# adapter.net
KiCad netlist of a schematic drawn in EAGLE
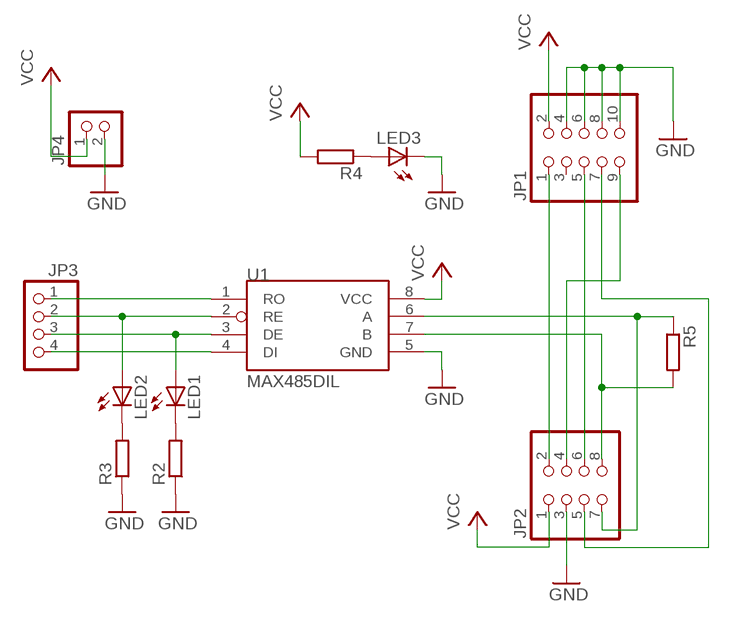
[diagram p0: schematic, sheet 1]

(export (version "E")
  (design (tool "Eeschema 10.0.6"))
  (components
    (comp (ref "JP1")
      (value "PINHD-2X5")
      (footprint "eagle-import:2X05")
      (libsource (lib "eagle-import") (part "PINHD-2X5"))
    )
    (comp (ref "JP2")
      (value "PINHD-2X4")
      (footprint "eagle-import:2X04")
      (libsource (lib "eagle-import") (part "PINHD-2X4"))
    )
    (comp (ref "JP3")
      (value "PINHD-1X4")
      (footprint "eagle-import:1X04")
      (libsource (lib "eagle-import") (part "PINHD-1X4"))
    )
    (comp (ref "JP4")
      (value "PINHD-1X2")
      (footprint "eagle-import:1X02")
      (libsource (lib "eagle-import") (part "PINHD-1X2"))
    )
    (comp (ref "LED1")
      (value "LEDCHIPLED_0805")
      (footprint "eagle-import:CHIPLED_0805")
      (libsource (lib "eagle-import") (part "LEDCHIPLED_0805"))
    )
    (comp (ref "LED2")
      (value "LEDCHIPLED_0805")
      (footprint "eagle-import:CHIPLED_0805")
      (libsource (lib "eagle-import") (part "LEDCHIPLED_0805"))
    )
    (comp (ref "LED3")
      (value "LEDCHIPLED_0805")
      (footprint "eagle-import:CHIPLED_0805")
      (libsource (lib "eagle-import") (part "LEDCHIPLED_0805"))
    )
    (comp (ref "R2")
      (value "R-EU_R0805")
      (footprint "eagle-import:R0805")
      (libsource (lib "eagle-import") (part "R-EU_R0805"))
    )
    (comp (ref "R3")
      (value "R-EU_R0805")
      (footprint "eagle-import:R0805")
      (libsource (lib "eagle-import") (part "R-EU_R0805"))
    )
    (comp (ref "R4")
      (value "R-EU_R0805")
      (footprint "eagle-import:R0805")
      (libsource (lib "eagle-import") (part "R-EU_R0805"))
    )
    (comp (ref "R5")
      (value "R-EU_R0805")
      (footprint "eagle-import:R0805")
      (libsource (lib "eagle-import") (part "R-EU_R0805"))
    )
    (comp (ref "U1")
      (value "MAX485DIL")
      (footprint "eagle-import:DIL08")
      (libsource (lib "eagle-import") (part "MAX485DIL"))
    )
  )
  (nets
    (net (code "1") (name "GND") (class "Default")
      (node (ref "JP1") (pin "10") (pinfunction "10_10") (pintype "passive"))
      (node (ref "JP1") (pin "4") (pinfunction "4_4") (pintype "passive"))
      (node (ref "JP1") (pin "6") (pinfunction "6_6") (pintype "passive"))
      (node (ref "JP1") (pin "8") (pinfunction "8_8") (pintype "passive"))
      (node (ref "JP2") (pin "3") (pinfunction "3_3") (pintype "passive"))
      (node (ref "JP4") (pin "2") (pinfunction "2_2") (pintype "passive"))
      (node (ref "LED3") (pin "C") (pinfunction "C_C") (pintype "passive"))
      (node (ref "R2") (pin "1") (pinfunction "1_1") (pintype "passive"))
      (node (ref "R3") (pin "1") (pinfunction "1_1") (pintype "passive"))
      (node (ref "U1") (pin "5") (pinfunction "GND_5") (pintype "bidirectional"))
    )
    (net (code "2") (name "Net-(JP1-Pad1)") (class "Default")
      (node (ref "JP1") (pin "1") (pinfunction "1_1") (pintype "passive"))
      (node (ref "JP2") (pin "2") (pinfunction "2_2") (pintype "passive"))
    )
    (net (code "3") (name "Net-(JP1-Pad5)") (class "Default")
      (node (ref "JP1") (pin "5") (pinfunction "5_5") (pintype "passive"))
      (node (ref "JP2") (pin "6") (pinfunction "6_6") (pintype "passive"))
    )
    (net (code "4") (name "Net-(JP1-Pad7)") (class "Default")
      (node (ref "JP1") (pin "7") (pinfunction "7_7") (pintype "passive"))
      (node (ref "JP2") (pin "5") (pinfunction "5_5") (pintype "passive"))
    )
    (net (code "5") (name "Net-(JP1-Pad9)") (class "Default")
      (node (ref "JP1") (pin "9") (pinfunction "9_9") (pintype "passive"))
      (node (ref "JP2") (pin "4") (pinfunction "4_4") (pintype "passive"))
    )
    (net (code "6") (name "Net-(LED1-PadC)") (class "Default")
      (node (ref "LED1") (pin "C") (pinfunction "C_C") (pintype "passive"))
      (node (ref "R2") (pin "2") (pinfunction "2_2") (pintype "passive"))
    )
    (net (code "7") (name "Net-(LED2-PadC)") (class "Default")
      (node (ref "LED2") (pin "C") (pinfunction "C_C") (pintype "passive"))
      (node (ref "R3") (pin "2") (pinfunction "2_2") (pintype "passive"))
    )
    (net (code "8") (name "Net-(LED3-PadA)") (class "Default")
      (node (ref "LED3") (pin "A") (pinfunction "A_A") (pintype "passive"))
      (node (ref "R4") (pin "1") (pinfunction "1_1") (pintype "passive"))
    )
    (net (code "9") (name "Net-(U1-A)") (class "Default")
      (node (ref "JP2") (pin "7") (pinfunction "7_7") (pintype "passive"))
      (node (ref "R5") (pin "1") (pinfunction "1_1") (pintype "passive"))
      (node (ref "U1") (pin "6") (pinfunction "A_6") (pintype "bidirectional"))
    )
    (net (code "10") (name "Net-(U1-B)") (class "Default")
      (node (ref "JP2") (pin "8") (pinfunction "8_8") (pintype "passive"))
      (node (ref "R5") (pin "2") (pinfunction "2_2") (pintype "passive"))
      (node (ref "U1") (pin "7") (pinfunction "B_7") (pintype "bidirectional"))
    )
    (net (code "11") (name "Net-(U1-DE)") (class "Default")
      (node (ref "JP3") (pin "3") (pinfunction "3_3") (pintype "passive"))
      (node (ref "LED1") (pin "A") (pinfunction "A_A") (pintype "passive"))
      (node (ref "U1") (pin "3") (pinfunction "DE_3") (pintype "bidirectional"))
    )
    (net (code "12") (name "Net-(U1-DI)") (class "Default")
      (node (ref "JP3") (pin "4") (pinfunction "4_4") (pintype "passive"))
      (node (ref "U1") (pin "4") (pinfunction "DI_4") (pintype "bidirectional"))
    )
    (net (code "13") (name "Net-(U1-RE)") (class "Default")
      (node (ref "JP3") (pin "2") (pinfunction "2_2") (pintype "passive"))
      (node (ref "LED2") (pin "A") (pinfunction "A_A") (pintype "passive"))
      (node (ref "U1") (pin "2") (pinfunction "RE_2") (pintype "bidirectional"))
    )
    (net (code "14") (name "Net-(U1-RO)") (class "Default")
      (node (ref "JP3") (pin "1") (pinfunction "1_1") (pintype "passive"))
      (node (ref "U1") (pin "1") (pinfunction "RO_1") (pintype "bidirectional"))
    )
    (net (code "15") (name "VCC") (class "Default")
      (node (ref "JP1") (pin "2") (pinfunction "2_2") (pintype "passive"))
      (node (ref "JP2") (pin "1") (pinfunction "1_1") (pintype "passive"))
      (node (ref "JP4") (pin "1") (pinfunction "1_1") (pintype "passive"))
      (node (ref "R4") (pin "2") (pinfunction "2_2") (pintype "passive"))
      (node (ref "U1") (pin "8") (pinfunction "VCC_8") (pintype "bidirectional"))
    )
    (net (code "16") (name "unconnected-(JP1-Pad3)") (class "Default")
      (node (ref "JP1") (pin "3") (pinfunction "3_3") (pintype "passive"))
    )
  )
)
